# nRF_prog_vusb.net
KiCad netlist of a schematic drawn in EAGLE
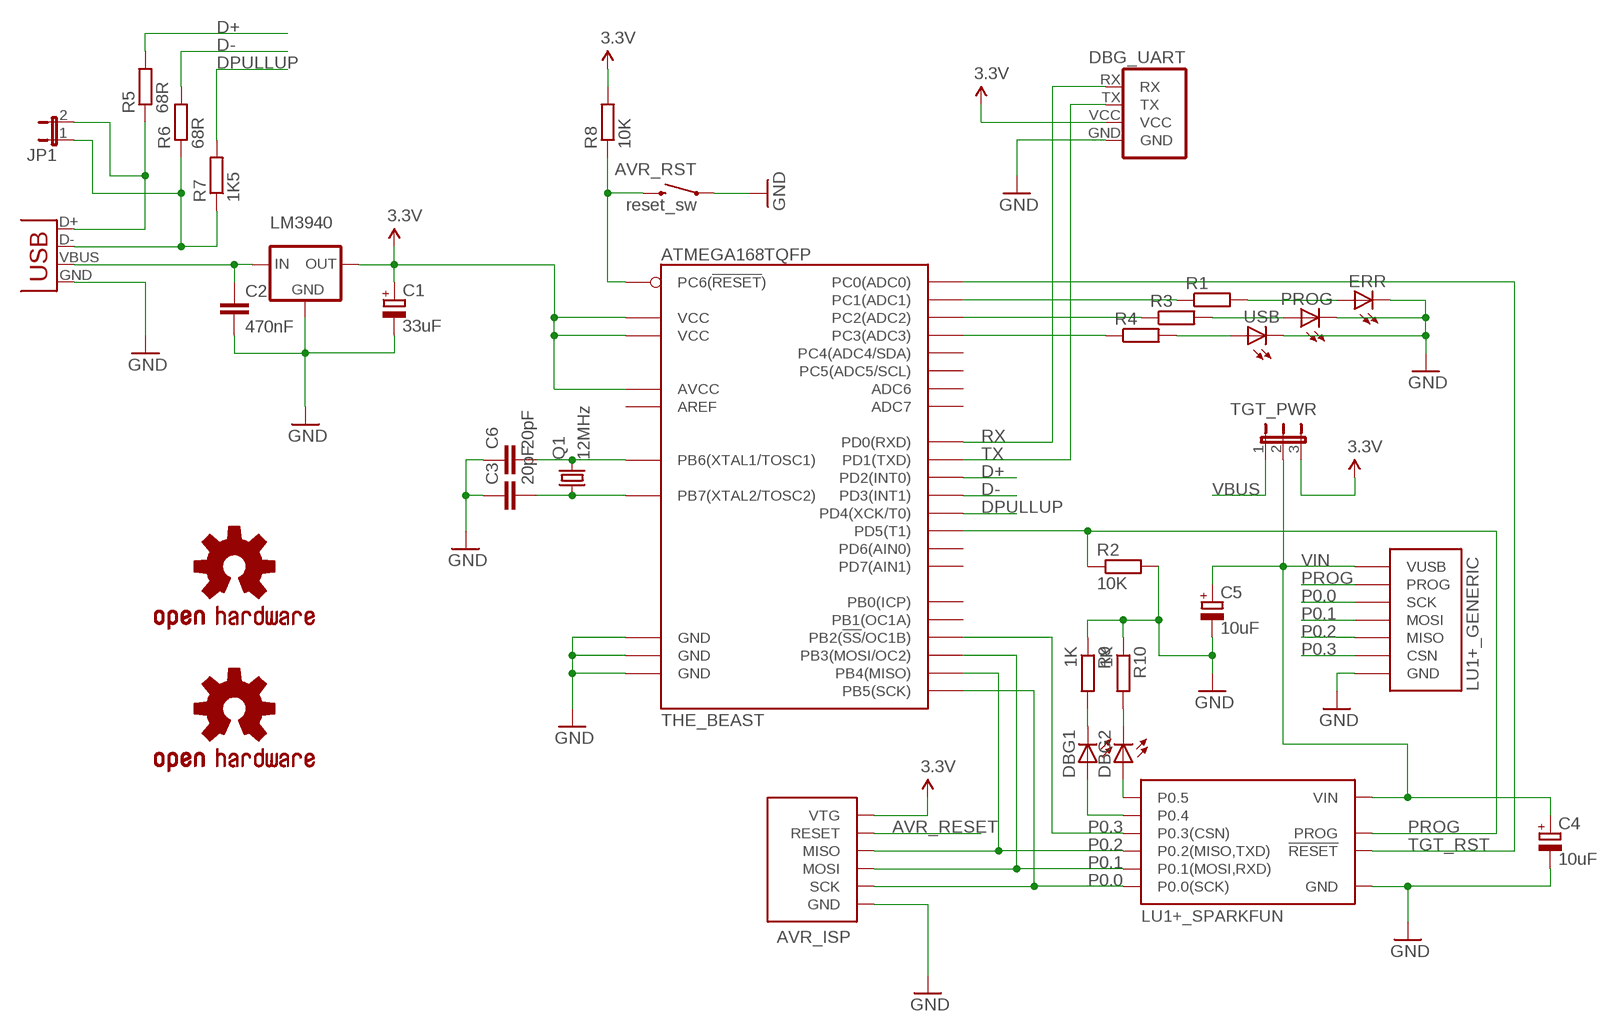
[diagram p0: schematic, sheet 1]

(export (version "E")
  (design (tool "Eeschema 10.0.6"))
  (components
    (comp (ref "AVR_ISP")
      (value "AVR-ISP-6SMALL_FP")
      (footprint "eagle-import:AVR-ISP-6-SMALL-FP")
      (libsource (lib "eagle-import") (part "AVR-ISP-6SMALL_FP"))
    )
    (comp (ref "AVR_RST")
      (value "reset_sw")
      (footprint "eagle-import:TACTILE_SWITCH_SMD")
      (libsource (lib "eagle-import") (part "SWITCH-MOMENTARY-2SMD"))
    )
    (comp (ref "C1")
      (value "33uF")
      (footprint "eagle-import:SMC_B")
      (libsource (lib "eagle-import") (part "CPOL-EUSMCB"))
    )
    (comp (ref "C2")
      (value "470nF")
      (footprint "eagle-import:C0805K")
      (libsource (lib "eagle-import") (part "C-EUC0805K"))
    )
    (comp (ref "C3")
      (value "20pF")
      (footprint "eagle-import:C0805")
      (libsource (lib "eagle-import") (part "C-EUC0805"))
    )
    (comp (ref "C4")
      (value "10uF")
      (footprint "eagle-import:SMC_B")
      (libsource (lib "eagle-import") (part "CPOL-EUSMCB"))
    )
    (comp (ref "C5")
      (value "10uF")
      (footprint "eagle-import:SMC_B")
      (libsource (lib "eagle-import") (part "CPOL-EUSMCB"))
    )
    (comp (ref "C6")
      (value "20pF")
      (footprint "eagle-import:C0805")
      (libsource (lib "eagle-import") (part "C-EUC0805"))
    )
    (comp (ref "DBG1")
      (value "LEDCHIPLED_0805")
      (footprint "eagle-import:CHIPLED_0805")
      (libsource (lib "eagle-import") (part "LEDCHIPLED_0805"))
    )
    (comp (ref "DBG2")
      (value "LEDCHIPLED_0805")
      (footprint "eagle-import:CHIPLED_0805")
      (libsource (lib "eagle-import") (part "LEDCHIPLED_0805"))
    )
    (comp (ref "DBG_UART")
      (value "UART_PORT")
      (footprint "eagle-import:UART_PORT")
      (libsource (lib "eagle-import") (part "UART_PORT"))
    )
    (comp (ref "ERR")
      (value "LEDCHIPLED_0805")
      (footprint "eagle-import:CHIPLED_0805")
      (libsource (lib "eagle-import") (part "LEDCHIPLED_0805"))
    )
    (comp (ref "JP1")
      (value "JP1E")
      (footprint "eagle-import:JP1")
      (libsource (lib "eagle-import") (part "JP1E"))
    )
    (comp (ref "LM3940")
      (value "LM3940")
      (footprint "eagle-import:SOT223")
      (libsource (lib "eagle-import") (part "LM3940"))
    )
    (comp (ref "LU1+_GENERIC")
      (value "NRF24LU1P_GENERIC")
      (footprint "eagle-import:NRF24LU1P_GENERIC")
      (libsource (lib "eagle-import") (part "NRF24LU1P_GENERIC"))
    )
    (comp (ref "LU1+_SPARKFUN")
      (value "NRF24LU1P_SPARKFUN_BREAKOUT")
      (footprint "eagle-import:NRF24LU+_SPARKFUN_BREAKOUT")
      (libsource (lib "eagle-import") (part "NRF24LU1P_SPARKFUN_BREAKOUT"))
    )
    (comp (ref "PROG")
      (value "LEDCHIPLED_0805")
      (footprint "eagle-import:CHIPLED_0805")
      (libsource (lib "eagle-import") (part "LEDCHIPLED_0805"))
    )
    (comp (ref "Q1")
      (value "12MHz")
      (footprint "eagle-import:QUARTZ")
      (libsource (lib "eagle-import") (part "CRYSTALHC49U-V"))
    )
    (comp (ref "R1")
      (value "R-EU_M0805")
      (footprint "eagle-import:M0805")
      (libsource (lib "eagle-import") (part "R-EU_M0805"))
    )
    (comp (ref "R2")
      (value "10K")
      (footprint "eagle-import:M0805")
      (libsource (lib "eagle-import") (part "R-EU_M0805"))
    )
    (comp (ref "R3")
      (value "R-EU_M0805")
      (footprint "eagle-import:M0805")
      (libsource (lib "eagle-import") (part "R-EU_M0805"))
    )
    (comp (ref "R4")
      (value "R-EU_M0805")
      (footprint "eagle-import:M0805")
      (libsource (lib "eagle-import") (part "R-EU_M0805"))
    )
    (comp (ref "R5")
      (value "68R")
      (footprint "eagle-import:M0805")
      (libsource (lib "eagle-import") (part "R-EU_M0805"))
    )
    (comp (ref "R6")
      (value "68R")
      (footprint "eagle-import:M0805")
      (libsource (lib "eagle-import") (part "R-EU_M0805"))
    )
    (comp (ref "R7")
      (value "1K5")
      (footprint "eagle-import:M0805")
      (libsource (lib "eagle-import") (part "R-EU_M0805"))
    )
    (comp (ref "R8")
      (value "10K")
      (footprint "eagle-import:M0805")
      (libsource (lib "eagle-import") (part "R-EU_M0805"))
    )
    (comp (ref "R9")
      (value "1K")
      (footprint "eagle-import:M0805")
      (libsource (lib "eagle-import") (part "R-EU_M0805"))
    )
    (comp (ref "R10")
      (value "1K")
      (footprint "eagle-import:M0805")
      (libsource (lib "eagle-import") (part "R-EU_M0805"))
    )
    (comp (ref "TGT_PWR")
      (value "JP2E")
      (footprint "eagle-import:JP2")
      (libsource (lib "eagle-import") (part "JP2E"))
    )
    (comp (ref "THE_BEAST")
      (value "ATMEGA168TQFP")
      (footprint "eagle-import:TQFP32-08")
      (libsource (lib "eagle-import") (part "ATMEGA168TQFP"))
    )
    (comp (ref "U$1")
      (value "OSHW-LOGOM")
      (footprint "eagle-import:OSHW-LOGO-M")
      (libsource (lib "eagle-import") (part "OSHW-LOGOM"))
    )
    (comp (ref "U$2")
      (value "OSHW-LOGOL")
      (footprint "eagle-import:OSHW-LOGO-L")
      (libsource (lib "eagle-import") (part "OSHW-LOGOL"))
    )
    (comp (ref "USB")
      (value "LEDCHIPLED_0805")
      (footprint "eagle-import:CHIPLED_0805")
      (libsource (lib "eagle-import") (part "LEDCHIPLED_0805"))
    )
    (comp (ref "USB-B")
      (value "USBPTH")
      (footprint "eagle-import:USB-B-PTH")
      (libsource (lib "eagle-import") (part "USBPTH"))
    )
  )
  (nets
    (net (code "1") (name "/AVR_RESET") (class "Default")
      (node (ref "AVR_ISP") (pin "RESET") (pinfunction "RESET_RESET") (pintype "passive"))
      (node (ref "AVR_RST") (pin "3") (pinfunction "2_3") (pintype "passive"))
      (node (ref "R8") (pin "1") (pinfunction "1_1") (pintype "passive"))
      (node (ref "THE_BEAST") (pin "29") (pinfunction "PC6(~{RESET})_29") (pintype "bidirectional"))
    )
    (net (code "2") (name "/D+") (class "Default")
      (node (ref "R5") (pin "2") (pinfunction "2_2") (pintype "passive"))
      (node (ref "THE_BEAST") (pin "32") (pinfunction "PD2(INT0)_32") (pintype "bidirectional"))
    )
    (net (code "3") (name "/D-") (class "Default")
      (node (ref "R6") (pin "2") (pinfunction "2_2") (pintype "passive"))
      (node (ref "THE_BEAST") (pin "1") (pinfunction "PD3(INT1)_1") (pintype "bidirectional"))
    )
    (net (code "4") (name "/DPULLUP") (class "Default")
      (node (ref "R7") (pin "2") (pinfunction "2_2") (pintype "passive"))
      (node (ref "THE_BEAST") (pin "2") (pinfunction "PD4(XCK/T0)_2") (pintype "bidirectional"))
    )
    (net (code "5") (name "/P0.0") (class "Default")
      (node (ref "AVR_ISP") (pin "SCK") (pinfunction "SCK_SCK") (pintype "passive"))
      (node (ref "LU1+_GENERIC") (pin "SCK") (pinfunction "SCK_SCK") (pintype "bidirectional"))
      (node (ref "LU1+_SPARKFUN") (pin "P0.0") (pinfunction "P0.0(SCK)_P0.0") (pintype "bidirectional"))
      (node (ref "THE_BEAST") (pin "17") (pinfunction "PB5(SCK)_17") (pintype "bidirectional"))
    )
    (net (code "6") (name "/P0.1") (class "Default")
      (node (ref "AVR_ISP") (pin "MOSI") (pinfunction "MOSI_MOSI") (pintype "passive"))
      (node (ref "LU1+_GENERIC") (pin "MOSI") (pinfunction "MOSI_MOSI") (pintype "bidirectional"))
      (node (ref "LU1+_SPARKFUN") (pin "P0.1") (pinfunction "P0.1(MOSI,RXD)_P0.1") (pintype "bidirectional"))
      (node (ref "THE_BEAST") (pin "15") (pinfunction "PB3(MOSI/OC2)_15") (pintype "bidirectional"))
    )
    (net (code "7") (name "/P0.2") (class "Default")
      (node (ref "AVR_ISP") (pin "MISO") (pinfunction "MISO_MISO") (pintype "passive"))
      (node (ref "LU1+_GENERIC") (pin "MISO") (pinfunction "MISO_MISO") (pintype "bidirectional"))
      (node (ref "LU1+_SPARKFUN") (pin "P0.2") (pinfunction "P0.2(MISO,TXD)_P0.2") (pintype "bidirectional"))
      (node (ref "THE_BEAST") (pin "16") (pinfunction "PB4(MISO)_16") (pintype "bidirectional"))
    )
    (net (code "8") (name "/P0.3") (class "Default")
      (node (ref "LU1+_GENERIC") (pin "CSN") (pinfunction "CSN_CSN") (pintype "bidirectional"))
      (node (ref "LU1+_SPARKFUN") (pin "P0.3") (pinfunction "P0.3(CSN)_P0.3") (pintype "bidirectional"))
      (node (ref "THE_BEAST") (pin "14") (pinfunction "PB2(~{SS}/OC1B)_14") (pintype "bidirectional"))
    )
    (net (code "9") (name "/PROG") (class "Default")
      (node (ref "LU1+_GENERIC") (pin "PROG") (pinfunction "PROG_PROG") (pintype "bidirectional"))
      (node (ref "LU1+_SPARKFUN") (pin "PROG") (pinfunction "PROG_PROG") (pintype "bidirectional"))
      (node (ref "R2") (pin "1") (pinfunction "1_1") (pintype "passive"))
      (node (ref "THE_BEAST") (pin "9") (pinfunction "PD5(T1)_9") (pintype "bidirectional"))
    )
    (net (code "10") (name "/RX") (class "Default")
      (node (ref "DBG_UART") (pin "RX") (pinfunction "RX_RX") (pintype "passive"))
      (node (ref "THE_BEAST") (pin "30") (pinfunction "PD0(RXD)_30") (pintype "bidirectional"))
    )
    (net (code "11") (name "/TGT_RST") (class "Default")
      (node (ref "LU1+_SPARKFUN") (pin "RESET") (pinfunction "~{RESET}_RESET") (pintype "bidirectional"))
      (node (ref "THE_BEAST") (pin "23") (pinfunction "PC0(ADC0)_23") (pintype "bidirectional"))
    )
    (net (code "12") (name "/TX") (class "Default")
      (node (ref "DBG_UART") (pin "TX") (pinfunction "TX_TX") (pintype "passive"))
      (node (ref "THE_BEAST") (pin "31") (pinfunction "PD1(TXD)_31") (pintype "bidirectional"))
    )
    (net (code "13") (name "/VBUS") (class "Default")
      (node (ref "C2") (pin "1") (pinfunction "1_1") (pintype "passive"))
      (node (ref "LM3940") (pin "1") (pinfunction "IN_1") (pintype "input"))
      (node (ref "TGT_PWR") (pin "1") (pinfunction "1_1") (pintype "passive"))
      (node (ref "USB-B") (pin "VBUS") (pinfunction "VBUS_VBUS") (pintype "bidirectional"))
    )
    (net (code "14") (name "/VIN") (class "Default")
      (node (ref "C4") (pin "+") (pinfunction "+_+") (pintype "passive"))
      (node (ref "C5") (pin "+") (pinfunction "+_+") (pintype "passive"))
      (node (ref "LU1+_GENERIC") (pin "VUSB") (pinfunction "VUSB_VUSB") (pintype "power_in"))
      (node (ref "LU1+_SPARKFUN") (pin "VIN") (pinfunction "VIN_VIN") (pintype "bidirectional"))
      (node (ref "TGT_PWR") (pin "2") (pinfunction "2_2") (pintype "passive"))
    )
    (net (code "15") (name "3.3V") (class "Default")
      (node (ref "AVR_ISP") (pin "VCC") (pinfunction "VTG_VCC") (pintype "passive"))
      (node (ref "C1") (pin "+") (pinfunction "+_+") (pintype "passive"))
      (node (ref "DBG_UART") (pin "VCC") (pinfunction "VCC_VCC") (pintype "passive"))
      (node (ref "LM3940") (pin "3") (pinfunction "OUT_3") (pintype "output"))
      (node (ref "R8") (pin "2") (pinfunction "2_2") (pintype "passive"))
      (node (ref "TGT_PWR") (pin "3") (pinfunction "3_3") (pintype "passive"))
      (node (ref "THE_BEAST") (pin "18") (pinfunction "AVCC_18") (pintype "input"))
      (node (ref "THE_BEAST") (pin "4") (pinfunction "VCC_4") (pintype "power_in"))
      (node (ref "THE_BEAST") (pin "6") (pinfunction "VCC_6") (pintype "power_in"))
    )
    (net (code "16") (name "GND") (class "Default")
      (node (ref "AVR_ISP") (pin "GND") (pinfunction "GND_GND") (pintype "passive"))
      (node (ref "AVR_RST") (pin "1") (pinfunction "1_1") (pintype "passive"))
      (node (ref "C1") (pin "-") (pinfunction "-_-") (pintype "passive"))
      (node (ref "C2") (pin "2") (pinfunction "2_2") (pintype "passive"))
      (node (ref "C3") (pin "1") (pinfunction "1_1") (pintype "passive"))
      (node (ref "C4") (pin "-") (pinfunction "-_-") (pintype "passive"))
      (node (ref "C5") (pin "-") (pinfunction "-_-") (pintype "passive"))
      (node (ref "C6") (pin "1") (pinfunction "1_1") (pintype "passive"))
      (node (ref "DBG_UART") (pin "GND") (pinfunction "GND_GND") (pintype "passive"))
      (node (ref "ERR") (pin "C") (pinfunction "C_C") (pintype "passive"))
      (node (ref "LM3940") (pin "2") (pinfunction "GND_2") (pintype "input"))
      (node (ref "LM3940") (pin "4") (pinfunction "GND_4") (pintype "input"))
      (node (ref "LU1+_GENERIC") (pin "GND") (pinfunction "GND_GND") (pintype "power_in"))
      (node (ref "LU1+_SPARKFUN") (pin "GND") (pinfunction "GND_GND") (pintype "bidirectional"))
      (node (ref "PROG") (pin "C") (pinfunction "C_C") (pintype "passive"))
      (node (ref "R10") (pin "1") (pinfunction "1_1") (pintype "passive"))
      (node (ref "R2") (pin "2") (pinfunction "2_2") (pintype "passive"))
      (node (ref "R9") (pin "1") (pinfunction "1_1") (pintype "passive"))
      (node (ref "THE_BEAST") (pin "21") (pinfunction "GND_21") (pintype "power_in"))
      (node (ref "THE_BEAST") (pin "3") (pinfunction "GND_3") (pintype "power_in"))
      (node (ref "THE_BEAST") (pin "5") (pinfunction "GND_5") (pintype "power_in"))
      (node (ref "USB") (pin "C") (pinfunction "C_C") (pintype "passive"))
      (node (ref "USB-B") (pin "GND") (pinfunction "GND_GND") (pintype "bidirectional"))
    )
    (net (code "17") (name "Net-(DBG1-PadA)") (class "Default")
      (node (ref "DBG1") (pin "A") (pinfunction "A_A") (pintype "passive"))
      (node (ref "LU1+_SPARKFUN") (pin "P0.4") (pinfunction "P0.4_P0.4") (pintype "bidirectional"))
    )
    (net (code "18") (name "Net-(DBG1-PadC)") (class "Default")
      (node (ref "DBG1") (pin "C") (pinfunction "C_C") (pintype "passive"))
      (node (ref "R9") (pin "2") (pinfunction "2_2") (pintype "passive"))
    )
    (net (code "19") (name "Net-(DBG2-PadA)") (class "Default")
      (node (ref "DBG2") (pin "A") (pinfunction "A_A") (pintype "passive"))
      (node (ref "LU1+_SPARKFUN") (pin "P0.5") (pinfunction "P0.5_P0.5") (pintype "bidirectional"))
    )
    (net (code "20") (name "Net-(DBG2-PadC)") (class "Default")
      (node (ref "DBG2") (pin "C") (pinfunction "C_C") (pintype "passive"))
      (node (ref "R10") (pin "2") (pinfunction "2_2") (pintype "passive"))
    )
    (net (code "21") (name "Net-(ERR-PadA)") (class "Default")
      (node (ref "ERR") (pin "A") (pinfunction "A_A") (pintype "passive"))
      (node (ref "R1") (pin "2") (pinfunction "2_2") (pintype "passive"))
    )
    (net (code "22") (name "Net-(JP1-Pad1)") (class "Default")
      (node (ref "JP1") (pin "1") (pinfunction "1_1") (pintype "passive"))
      (node (ref "R6") (pin "1") (pinfunction "1_1") (pintype "passive"))
      (node (ref "R7") (pin "1") (pinfunction "1_1") (pintype "passive"))
      (node (ref "USB-B") (pin "D-") (pinfunction "D-_D-") (pintype "bidirectional"))
    )
    (net (code "23") (name "Net-(JP1-Pad2)") (class "Default")
      (node (ref "JP1") (pin "2") (pinfunction "2_2") (pintype "passive"))
      (node (ref "R5") (pin "1") (pinfunction "1_1") (pintype "passive"))
      (node (ref "USB-B") (pin "D+") (pinfunction "D+_D+") (pintype "bidirectional"))
    )
    (net (code "24") (name "Net-(PROG-PadA)") (class "Default")
      (node (ref "PROG") (pin "A") (pinfunction "A_A") (pintype "passive"))
      (node (ref "R3") (pin "2") (pinfunction "2_2") (pintype "passive"))
    )
    (net (code "25") (name "Net-(R4-Pad2)") (class "Default")
      (node (ref "R4") (pin "2") (pinfunction "2_2") (pintype "passive"))
      (node (ref "USB") (pin "A") (pinfunction "A_A") (pintype "passive"))
    )
    (net (code "26") (name "Net-(THE_BEAST-PB6(XTAL1{slash}TOSC1))") (class "Default")
      (node (ref "C6") (pin "2") (pinfunction "2_2") (pintype "passive"))
      (node (ref "Q1") (pin "2") (pinfunction "2_2") (pintype "passive"))
      (node (ref "THE_BEAST") (pin "7") (pinfunction "PB6(XTAL1/TOSC1)_7") (pintype "bidirectional"))
    )
    (net (code "27") (name "Net-(THE_BEAST-PB7(XTAL2{slash}TOSC2))") (class "Default")
      (node (ref "C3") (pin "2") (pinfunction "2_2") (pintype "passive"))
      (node (ref "Q1") (pin "1") (pinfunction "1_1") (pintype "passive"))
      (node (ref "THE_BEAST") (pin "8") (pinfunction "PB7(XTAL2/TOSC2)_8") (pintype "bidirectional"))
    )
    (net (code "28") (name "Net-(THE_BEAST-PC1(ADC1))") (class "Default")
      (node (ref "R1") (pin "1") (pinfunction "1_1") (pintype "passive"))
      (node (ref "THE_BEAST") (pin "24") (pinfunction "PC1(ADC1)_24") (pintype "bidirectional"))
    )
    (net (code "29") (name "Net-(THE_BEAST-PC2(ADC2))") (class "Default")
      (node (ref "R3") (pin "1") (pinfunction "1_1") (pintype "passive"))
      (node (ref "THE_BEAST") (pin "25") (pinfunction "PC2(ADC2)_25") (pintype "bidirectional"))
    )
    (net (code "30") (name "Net-(THE_BEAST-PC3(ADC3))") (class "Default")
      (node (ref "R4") (pin "1") (pinfunction "1_1") (pintype "passive"))
      (node (ref "THE_BEAST") (pin "26") (pinfunction "PC3(ADC3)_26") (pintype "bidirectional"))
    )
    (net (code "31") (name "unconnected-(THE_BEAST-ADC6-Pad19)") (class "Default")
      (node (ref "THE_BEAST") (pin "19") (pinfunction "ADC6_19") (pintype "bidirectional"))
    )
    (net (code "32") (name "unconnected-(THE_BEAST-ADC7-Pad22)") (class "Default")
      (node (ref "THE_BEAST") (pin "22") (pinfunction "ADC7_22") (pintype "bidirectional"))
    )
    (net (code "33") (name "unconnected-(THE_BEAST-AREF-Pad20)") (class "Default")
      (node (ref "THE_BEAST") (pin "20") (pinfunction "AREF_20") (pintype "input"))
    )
    (net (code "34") (name "unconnected-(THE_BEAST-PB0(ICP)-Pad12)") (class "Default")
      (node (ref "THE_BEAST") (pin "12") (pinfunction "PB0(ICP)_12") (pintype "bidirectional"))
    )
    (net (code "35") (name "unconnected-(THE_BEAST-PB1(OC1A)-Pad13)") (class "Default")
      (node (ref "THE_BEAST") (pin "13") (pinfunction "PB1(OC1A)_13") (pintype "bidirectional"))
    )
    (net (code "36") (name "unconnected-(THE_BEAST-PC4(ADC4{slash}SDA)-Pad27)") (class "Default")
      (node (ref "THE_BEAST") (pin "27") (pinfunction "PC4(ADC4/SDA)_27") (pintype "bidirectional"))
    )
    (net (code "37") (name "unconnected-(THE_BEAST-PC5(ADC5{slash}SCL)-Pad28)") (class "Default")
      (node (ref "THE_BEAST") (pin "28") (pinfunction "PC5(ADC5/SCL)_28") (pintype "bidirectional"))
    )
    (net (code "38") (name "unconnected-(THE_BEAST-PD6(AIN0)-Pad10)") (class "Default")
      (node (ref "THE_BEAST") (pin "10") (pinfunction "PD6(AIN0)_10") (pintype "bidirectional"))
    )
    (net (code "39") (name "unconnected-(THE_BEAST-PD7(AIN1)-Pad11)") (class "Default")
      (node (ref "THE_BEAST") (pin "11") (pinfunction "PD7(AIN1)_11") (pintype "bidirectional"))
    )
  )
)
